# NGUYEN_LI.net
KiCad netlist of a schematic drawn in Altium Designer
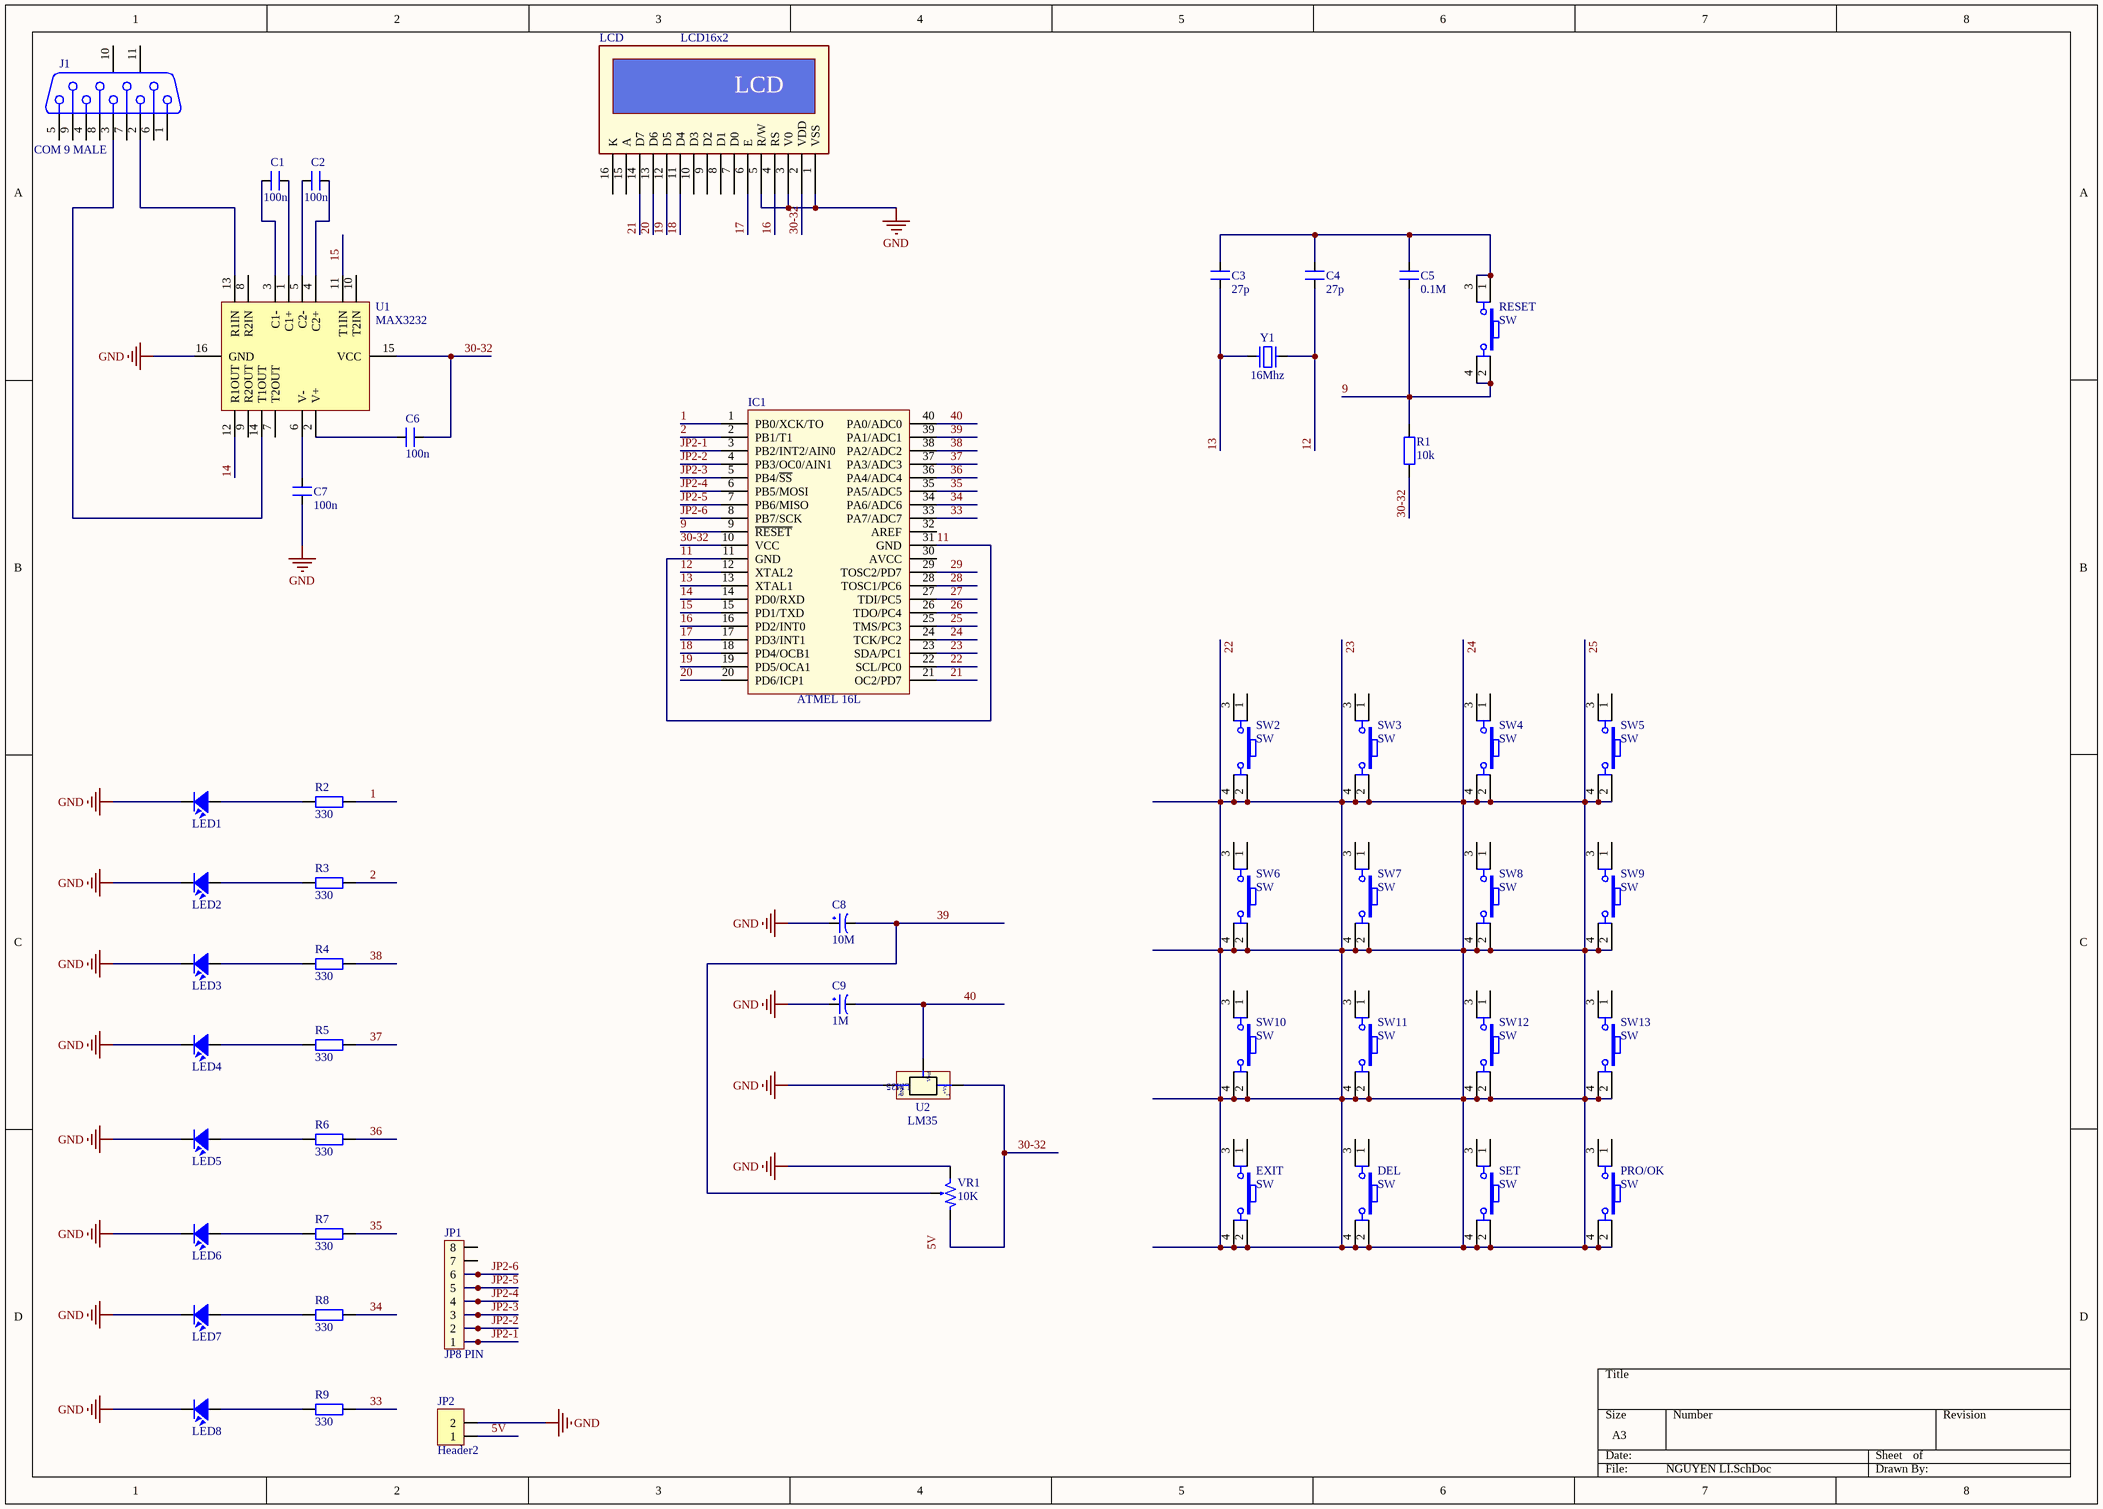
[diagram p0: NGUYEN LI.SchDoc]

(export (version "E")
  (design (tool "Eeschema 10.0.6"))
  (components
    (comp (ref "C1")
      (value "100n")
      (footprint "CN1")
      (description "Cap np  1pF - 472pF")
      (libsource (lib "Devzone_SCHLib") (part "CN1"))
    )
    (comp (ref "C2")
      (value "100n")
      (footprint "CN1")
      (description "Cap np  1pF - 472pF")
      (libsource (lib "Devzone_SCHLib") (part "CN1"))
    )
    (comp (ref "C3")
      (value "27p")
      (footprint "CN1")
      (description "Cap np  1pF - 472pF")
      (libsource (lib "syhaunguyen") (part "CN1"))
    )
    (comp (ref "C4")
      (value "27p")
      (footprint "CN1")
      (description "Cap np  1pF - 472pF")
      (libsource (lib "syhaunguyen") (part "CN1"))
    )
    (comp (ref "C5")
      (value "0.1M")
      (footprint "CN1")
      (description "Cap np  1pF - 472pF")
      (libsource (lib "syhaunguyen") (part "CN1"))
    )
    (comp (ref "C6")
      (value "100n")
      (footprint "CN1")
      (description "Cap np  1pF - 472pF")
      (libsource (lib "Devzone_SCHLib") (part "CN1"))
    )
    (comp (ref "C7")
      (value "100n")
      (footprint "CN1")
      (description "Cap np  1pF - 472pF")
      (libsource (lib "Devzone_SCHLib") (part "CN1"))
    )
    (comp (ref "C8")
      (value "10M")
      (footprint "CP1.5/3.4")
      (description "Cap 1000uF/16V - 220uF/50V")
      (libsource (lib "My Library (1)") (part "CP4"))
    )
    (comp (ref "C9")
      (value "1M")
      (footprint "CP1.5/3.4")
      (description "Cap 1000uF/16V - 220uF/50V")
      (libsource (lib "My Library (1)") (part "CP4"))
    )
    (comp (ref "DEL")
      (value "SW")
      (footprint "SW4B")
      (description "Switch button 4 pin")
      (libsource (lib "My Library (1)") (part "SW4"))
    )
    (comp (ref "EXIT")
      (value "SW")
      (footprint "SW4B")
      (description "Switch button 4 pin")
      (libsource (lib "My Library (1)") (part "SW4"))
    )
    (comp (ref "IC1")
      (value "ATMEL 16L")
      (footprint "DIP40/W0.6")
      (description "8-Bit AVR Microcontroller with 16K Bytes of In-System Programmable Flash Memory")
      (libsource (lib "Cty1") (part "Atmega16L"))
    )
    (comp (ref "J1")
      (value "COM 9 MALE")
      (footprint "DSB 9-M")
      (description "COM 9")
      (fields (field (name "PUBLISHER") "Altium Limited"))
      (libsource (lib "My Library (1)") (part "DSB9M"))
    )
    (comp (ref "JP1") (value "JP8 PIN") (footprint "JP8") (libsource (lib "My Library (1)") (part "JP8")))
    (comp (ref "JP2")
      (value "Header2")
      (footprint "Header2")
      (description "Header IDC, 2 x 1 Pin Vertical 2.54mm Pitch (Non-Boxed, Male)")
      (fields
        (field (name "MANUFACTURER") "Würth Elektronik eiSos GmbH")
        (field (name "PARTNO") "613002143121")
        (field (name "CREATED BY") "Karrer Zheng")
      )
      (libsource (lib "My Library (1)") (part "Header2"))
    )
    (comp (ref "LCD")
      (value "LCD16x2")
      (footprint "LCD16X2")
      (libsource (lib "Devzone_SCHLib") (part "LCD Text"))
    )
    (comp (ref "LED1")
      (value "LED")
      (footprint "LED-3")
      (description "LED Single colour Green and Red")
      (libsource (lib "syhaunguyen") (part "LED"))
    )
    (comp (ref "LED2")
      (value "LED")
      (footprint "LED-3")
      (description "LED Single colour Green and Red")
      (libsource (lib "syhaunguyen") (part "LED"))
    )
    (comp (ref "LED3")
      (value "LED")
      (footprint "LED-3")
      (description "LED Single colour Green and Red")
      (libsource (lib "syhaunguyen") (part "LED"))
    )
    (comp (ref "LED4")
      (value "LED")
      (footprint "LED-3")
      (description "LED Single colour Green and Red")
      (libsource (lib "syhaunguyen") (part "LED"))
    )
    (comp (ref "LED5")
      (value "LED")
      (footprint "LED-3")
      (description "LED Single colour Green and Red")
      (libsource (lib "syhaunguyen") (part "LED"))
    )
    (comp (ref "LED6")
      (value "LED")
      (footprint "LED-3")
      (description "LED Single colour Green and Red")
      (libsource (lib "syhaunguyen") (part "LED"))
    )
    (comp (ref "LED7")
      (value "LED")
      (footprint "LED-3")
      (description "LED Single colour Green and Red")
      (libsource (lib "syhaunguyen") (part "LED"))
    )
    (comp (ref "LED8")
      (value "LED")
      (footprint "LED-3")
      (description "LED Single colour Green and Red")
      (libsource (lib "syhaunguyen") (part "LED"))
    )
    (comp (ref "PRO/OK")
      (value "SW")
      (footprint "SW4B")
      (description "Switch button 4 pin")
      (libsource (lib "My Library (1)") (part "SW4"))
    )
    (comp (ref "R1")
      (value "10k")
      (footprint "R1/4W")
      (description "Resistor 1/4W")
      (libsource (lib "syhaunguyen") (part "R1/4W"))
    )
    (comp (ref "R2")
      (value "330")
      (footprint "R1/4W")
      (description "Resistor 1/4W")
      (libsource (lib "syhaunguyen") (part "R1/4W"))
    )
    (comp (ref "R3")
      (value "330")
      (footprint "R1/4W")
      (description "Resistor 1/4W")
      (libsource (lib "syhaunguyen") (part "R1/4W"))
    )
    (comp (ref "R4")
      (value "330")
      (footprint "R1/4W")
      (description "Resistor 1/4W")
      (libsource (lib "syhaunguyen") (part "R1/4W"))
    )
    (comp (ref "R5")
      (value "330")
      (footprint "R1/4W")
      (description "Resistor 1/4W")
      (libsource (lib "syhaunguyen") (part "R1/4W"))
    )
    (comp (ref "R6")
      (value "330")
      (footprint "R1/4W")
      (description "Resistor 1/4W")
      (libsource (lib "syhaunguyen") (part "R1/4W"))
    )
    (comp (ref "R7")
      (value "330")
      (footprint "R1/4W")
      (description "Resistor 1/4W")
      (libsource (lib "syhaunguyen") (part "R1/4W"))
    )
    (comp (ref "R8")
      (value "330")
      (footprint "R1/4W")
      (description "Resistor 1/4W")
      (libsource (lib "syhaunguyen") (part "R1/4W"))
    )
    (comp (ref "R9")
      (value "330")
      (footprint "R1/4W")
      (description "Resistor 1/4W")
      (libsource (lib "syhaunguyen") (part "R1/4W"))
    )
    (comp (ref "RESET")
      (value "SW")
      (footprint "SW4B")
      (description "Switch button 4 pin")
      (libsource (lib "My Library (1)") (part "SW4"))
    )
    (comp (ref "SET")
      (value "SW")
      (footprint "SW4B")
      (description "Switch button 4 pin")
      (libsource (lib "My Library (1)") (part "SW4"))
    )
    (comp (ref "SW2")
      (value "SW")
      (footprint "SW4B")
      (description "Switch button 4 pin")
      (libsource (lib "My Library (1)") (part "SW4"))
    )
    (comp (ref "SW3")
      (value "SW")
      (footprint "SW4B")
      (description "Switch button 4 pin")
      (libsource (lib "My Library (1)") (part "SW4"))
    )
    (comp (ref "SW4")
      (value "SW")
      (footprint "SW4B")
      (description "Switch button 4 pin")
      (libsource (lib "My Library (1)") (part "SW4"))
    )
    (comp (ref "SW5")
      (value "SW")
      (footprint "SW4B")
      (description "Switch button 4 pin")
      (libsource (lib "My Library (1)") (part "SW4"))
    )
    (comp (ref "SW6")
      (value "SW")
      (footprint "SW4B")
      (description "Switch button 4 pin")
      (libsource (lib "My Library (1)") (part "SW4"))
    )
    (comp (ref "SW7")
      (value "SW")
      (footprint "SW4B")
      (description "Switch button 4 pin")
      (libsource (lib "My Library (1)") (part "SW4"))
    )
    (comp (ref "SW8")
      (value "SW")
      (footprint "SW4B")
      (description "Switch button 4 pin")
      (libsource (lib "My Library (1)") (part "SW4"))
    )
    (comp (ref "SW9")
      (value "SW")
      (footprint "SW4B")
      (description "Switch button 4 pin")
      (libsource (lib "My Library (1)") (part "SW4"))
    )
    (comp (ref "SW10")
      (value "SW")
      (footprint "SW4B")
      (description "Switch button 4 pin")
      (libsource (lib "My Library (1)") (part "SW4"))
    )
    (comp (ref "SW11")
      (value "SW")
      (footprint "SW4B")
      (description "Switch button 4 pin")
      (libsource (lib "My Library (1)") (part "SW4"))
    )
    (comp (ref "SW12")
      (value "SW")
      (footprint "SW4B")
      (description "Switch button 4 pin")
      (libsource (lib "My Library (1)") (part "SW4"))
    )
    (comp (ref "SW13")
      (value "SW")
      (footprint "SW4B")
      (description "Switch button 4 pin")
      (libsource (lib "My Library (1)") (part "SW4"))
    )
    (comp (ref "U1")
      (value "MAX3232")
      (footprint "DIP16")
      (fields
        (field (name "MANUFACTURER PART NUMBER") "MAX232DR")
        (field (name "MANUFACTURER") "Texas Instruments")
      )
      (libsource (lib "TechMT.VN_Lib_Project v2") (part "MAX3232"))
    )
    (comp (ref "U2")
      (value "LM35")
      (footprint "QTO-92")
      (description "Teminal")
      (libsource (lib "My Library (1)") (part "LM35"))
    )
    (comp (ref "VR1")
      (value "10K")
      (footprint "VR1")
      (description "Var Resistor")
      (libsource (lib "My Library (1)") (part "VR1"))
    )
    (comp (ref "Y1")
      (value "16Mhz")
      (footprint "XT2")
      (description "Crystal For all Crystal 2pin.")
      (libsource (lib "syhaunguyen") (part "XT2"))
    )
  )
  (nets
    (net (code "1") (name "/1") (class "Default")
      (node (ref "IC1") (pin "1") (pinfunction "PB0/XCK/TO_1") (pintype "passive"))
      (node (ref "R2") (pin "2") (pinfunction "2_2") (pintype "passive"))
    )
    (net (code "2") (name "/2") (class "Default")
      (node (ref "IC1") (pin "2") (pinfunction "PB1/T1_2") (pintype "passive"))
      (node (ref "R3") (pin "2") (pinfunction "2_2") (pintype "passive"))
    )
    (net (code "3") (name "/5V") (class "Default")
      (node (ref "JP2") (pin "1") (pinfunction "1_1") (pintype "passive"))
    )
    (net (code "4") (name "/9") (class "Default")
      (node (ref "C5") (pin "2") (pinfunction "2_2") (pintype "passive"))
      (node (ref "IC1") (pin "9") (pinfunction "~{RESET}_9") (pintype "passive"))
      (node (ref "R1") (pin "1") (pinfunction "1_1") (pintype "passive"))
      (node (ref "RESET") (pin "2") (pintype "passive"))
      (node (ref "RESET") (pin "4") (pintype "passive"))
    )
    (net (code "5") (name "/11") (class "Default")
      (node (ref "IC1") (pin "11") (pinfunction "GND_11") (pintype "passive"))
      (node (ref "IC1") (pin "31") (pinfunction "GND_31") (pintype "passive"))
    )
    (net (code "6") (name "/12") (class "Default")
      (node (ref "C4") (pin "2") (pinfunction "2_2") (pintype "passive"))
      (node (ref "IC1") (pin "12") (pinfunction "XTAL2_12") (pintype "passive"))
      (node (ref "Y1") (pin "2") (pinfunction "2_2") (pintype "passive"))
    )
    (net (code "7") (name "/13") (class "Default")
      (node (ref "C3") (pin "2") (pinfunction "2_2") (pintype "passive"))
      (node (ref "IC1") (pin "13") (pinfunction "XTAL1_13") (pintype "passive"))
      (node (ref "Y1") (pin "1") (pinfunction "1_1") (pintype "passive"))
    )
    (net (code "8") (name "/14") (class "Default")
      (node (ref "IC1") (pin "14") (pinfunction "PD0/RXD_14") (pintype "passive"))
      (node (ref "U1") (pin "12") (pinfunction "R1OUT_12") (pintype "passive"))
    )
    (net (code "9") (name "/15") (class "Default")
      (node (ref "IC1") (pin "15") (pinfunction "PD1/TXD_15") (pintype "passive"))
      (node (ref "U1") (pin "11") (pinfunction "T1IN_11") (pintype "passive"))
    )
    (net (code "10") (name "/16") (class "Default")
      (node (ref "IC1") (pin "16") (pinfunction "PD2/INT0_16") (pintype "passive"))
      (node (ref "LCD") (pin "4") (pinfunction "RS_4") (pintype "passive"))
    )
    (net (code "11") (name "/17") (class "Default")
      (node (ref "IC1") (pin "17") (pinfunction "PD3/INT1_17") (pintype "passive"))
      (node (ref "LCD") (pin "6") (pinfunction "E_6") (pintype "passive"))
    )
    (net (code "12") (name "/18") (class "Default")
      (node (ref "IC1") (pin "18") (pinfunction "PD4/OCB1_18") (pintype "passive"))
      (node (ref "LCD") (pin "11") (pinfunction "D4_11") (pintype "passive"))
    )
    (net (code "13") (name "/19") (class "Default")
      (node (ref "IC1") (pin "19") (pinfunction "PD5/OCA1_19") (pintype "passive"))
      (node (ref "LCD") (pin "12") (pinfunction "D5_12") (pintype "passive"))
    )
    (net (code "14") (name "/20") (class "Default")
      (node (ref "IC1") (pin "20") (pinfunction "PD6/ICP1_20") (pintype "passive"))
      (node (ref "LCD") (pin "13") (pinfunction "D6_13") (pintype "passive"))
    )
    (net (code "15") (name "/21") (class "Default")
      (node (ref "IC1") (pin "21") (pinfunction "OC2/PD7_21") (pintype "passive"))
      (node (ref "LCD") (pin "14") (pinfunction "D7_14") (pintype "passive"))
    )
    (net (code "16") (name "/22") (class "Default")
      (node (ref "DEL") (pin "2") (pintype "passive"))
      (node (ref "DEL") (pin "4") (pintype "passive"))
      (node (ref "EXIT") (pin "2") (pintype "passive"))
      (node (ref "EXIT") (pin "4") (pintype "passive"))
      (node (ref "IC1") (pin "22") (pinfunction "SCL/PC0_22") (pintype "passive"))
      (node (ref "IC1") (pin "23") (pinfunction "SDA/PC1_23") (pintype "passive"))
      (node (ref "IC1") (pin "24") (pinfunction "TCK/PC2_24") (pintype "passive"))
      (node (ref "IC1") (pin "25") (pinfunction "TMS/PC3_25") (pintype "passive"))
      (node (ref "PRO/OK") (pin "2") (pintype "passive"))
      (node (ref "PRO/OK") (pin "4") (pintype "passive"))
      (node (ref "SET") (pin "2") (pintype "passive"))
      (node (ref "SET") (pin "4") (pintype "passive"))
      (node (ref "SW10") (pin "2") (pintype "passive"))
      (node (ref "SW10") (pin "4") (pintype "passive"))
      (node (ref "SW11") (pin "2") (pintype "passive"))
      (node (ref "SW11") (pin "4") (pintype "passive"))
      (node (ref "SW12") (pin "2") (pintype "passive"))
      (node (ref "SW12") (pin "4") (pintype "passive"))
      (node (ref "SW13") (pin "2") (pintype "passive"))
      (node (ref "SW13") (pin "4") (pintype "passive"))
      (node (ref "SW2") (pin "2") (pintype "passive"))
      (node (ref "SW2") (pin "4") (pintype "passive"))
      (node (ref "SW3") (pin "2") (pintype "passive"))
      (node (ref "SW3") (pin "4") (pintype "passive"))
      (node (ref "SW4") (pin "2") (pintype "passive"))
      (node (ref "SW4") (pin "4") (pintype "passive"))
      (node (ref "SW5") (pin "2") (pintype "passive"))
      (node (ref "SW5") (pin "4") (pintype "passive"))
      (node (ref "SW6") (pin "2") (pintype "passive"))
      (node (ref "SW6") (pin "4") (pintype "passive"))
      (node (ref "SW7") (pin "2") (pintype "passive"))
      (node (ref "SW7") (pin "4") (pintype "passive"))
      (node (ref "SW8") (pin "2") (pintype "passive"))
      (node (ref "SW8") (pin "4") (pintype "passive"))
      (node (ref "SW9") (pin "2") (pintype "passive"))
      (node (ref "SW9") (pin "4") (pintype "passive"))
    )
    (net (code "17") (name "/26") (class "Default")
      (node (ref "IC1") (pin "26") (pinfunction "TDO/PC4_26") (pintype "passive"))
    )
    (net (code "18") (name "/27") (class "Default")
      (node (ref "IC1") (pin "27") (pinfunction "TDI/PC5_27") (pintype "passive"))
    )
    (net (code "19") (name "/28") (class "Default")
      (node (ref "IC1") (pin "28") (pinfunction "TOSC1/PC6_28") (pintype "passive"))
    )
    (net (code "20") (name "/29") (class "Default")
      (node (ref "IC1") (pin "29") (pinfunction "TOSC2/PD7_29") (pintype "passive"))
    )
    (net (code "21") (name "/30-32") (class "Default")
      (node (ref "C6") (pin "2") (pinfunction "2_2") (pintype "passive"))
      (node (ref "IC1") (pin "10") (pinfunction "VCC_10") (pintype "passive"))
      (node (ref "LCD") (pin "2") (pinfunction "VDD_2") (pintype "passive"))
      (node (ref "R1") (pin "2") (pinfunction "2_2") (pintype "passive"))
      (node (ref "U1") (pin "15") (pinfunction "VCC_15") (pintype "power_in"))
      (node (ref "U2") (pin "1") (pinfunction "+Vs_1") (pintype "passive"))
      (node (ref "VR1") (pin "1") (pinfunction "1_1") (pintype "passive"))
    )
    (net (code "22") (name "/33") (class "Default")
      (node (ref "IC1") (pin "33") (pinfunction "PA7/ADC7_33") (pintype "passive"))
      (node (ref "R9") (pin "2") (pinfunction "2_2") (pintype "passive"))
    )
    (net (code "23") (name "/34") (class "Default")
      (node (ref "IC1") (pin "34") (pinfunction "PA6/ADC6_34") (pintype "passive"))
      (node (ref "R8") (pin "2") (pinfunction "2_2") (pintype "passive"))
    )
    (net (code "24") (name "/35") (class "Default")
      (node (ref "IC1") (pin "35") (pinfunction "PA5/ADC5_35") (pintype "passive"))
      (node (ref "R7") (pin "2") (pinfunction "2_2") (pintype "passive"))
    )
    (net (code "25") (name "/36") (class "Default")
      (node (ref "IC1") (pin "36") (pinfunction "PA4/ADC4_36") (pintype "passive"))
      (node (ref "R6") (pin "2") (pinfunction "2_2") (pintype "passive"))
    )
    (net (code "26") (name "/37") (class "Default")
      (node (ref "IC1") (pin "37") (pinfunction "PA3/ADC3_37") (pintype "passive"))
      (node (ref "R5") (pin "2") (pinfunction "2_2") (pintype "passive"))
    )
    (net (code "27") (name "/38") (class "Default")
      (node (ref "IC1") (pin "38") (pinfunction "PA2/ADC2_38") (pintype "passive"))
      (node (ref "R4") (pin "2") (pinfunction "2_2") (pintype "passive"))
    )
    (net (code "28") (name "/39") (class "Default")
      (node (ref "C8") (pin "2") (pinfunction "2_2") (pintype "passive"))
      (node (ref "IC1") (pin "39") (pinfunction "PA1/ADC1_39") (pintype "passive"))
      (node (ref "VR1") (pin "2") (pinfunction "2_2") (pintype "passive"))
    )
    (net (code "29") (name "/40") (class "Default")
      (node (ref "C9") (pin "2") (pinfunction "2_2") (pintype "passive"))
      (node (ref "IC1") (pin "40") (pinfunction "PA0/ADC0_40") (pintype "passive"))
      (node (ref "U2") (pin "2") (pinfunction "Vout_2") (pintype "passive"))
    )
    (net (code "30") (name "/JP2-1") (class "Default")
      (node (ref "IC1") (pin "3") (pinfunction "PB2/INT2/AIN0_3") (pintype "passive"))
      (node (ref "JP1") (pin "1") (pinfunction "1_1") (pintype "passive"))
    )
    (net (code "31") (name "/JP2-2") (class "Default")
      (node (ref "IC1") (pin "4") (pinfunction "PB3/OC0/AIN1_4") (pintype "passive"))
      (node (ref "JP1") (pin "2") (pinfunction "2_2") (pintype "passive"))
    )
    (net (code "32") (name "/JP2-3") (class "Default")
      (node (ref "IC1") (pin "5") (pinfunction "PB4/~{SS}_5") (pintype "passive"))
      (node (ref "JP1") (pin "3") (pinfunction "3_3") (pintype "passive"))
    )
    (net (code "33") (name "/JP2-4") (class "Default")
      (node (ref "IC1") (pin "6") (pinfunction "PB5/MOSI_6") (pintype "passive"))
      (node (ref "JP1") (pin "4") (pinfunction "4_4") (pintype "passive"))
    )
    (net (code "34") (name "/JP2-5") (class "Default")
      (node (ref "IC1") (pin "7") (pinfunction "PB6/MISO_7") (pintype "passive"))
      (node (ref "JP1") (pin "5") (pinfunction "5_5") (pintype "passive"))
    )
    (net (code "35") (name "/JP2-6") (class "Default")
      (node (ref "IC1") (pin "8") (pinfunction "PB7/SCK_8") (pintype "passive"))
      (node (ref "JP1") (pin "6") (pinfunction "6_6") (pintype "passive"))
    )
    (net (code "36") (name "GND") (class "Default")
      (node (ref "C7") (pin "1") (pinfunction "1_1") (pintype "passive"))
      (node (ref "C8") (pin "1") (pinfunction "1_1") (pintype "passive"))
      (node (ref "C9") (pin "1") (pinfunction "1_1") (pintype "passive"))
      (node (ref "JP2") (pin "2") (pinfunction "2_2") (pintype "passive"))
      (node (ref "LCD") (pin "1") (pinfunction "VSS_1") (pintype "passive"))
      (node (ref "LCD") (pin "3") (pinfunction "V0_3") (pintype "passive"))
      (node (ref "LCD") (pin "5") (pinfunction "R/W_5") (pintype "passive"))
      (node (ref "LED1") (pin "2") (pinfunction "2_2") (pintype "passive"))
      (node (ref "LED2") (pin "2") (pinfunction "2_2") (pintype "passive"))
      (node (ref "LED3") (pin "2") (pinfunction "2_2") (pintype "passive"))
      (node (ref "LED4") (pin "2") (pinfunction "2_2") (pintype "passive"))
      (node (ref "LED5") (pin "2") (pinfunction "2_2") (pintype "passive"))
      (node (ref "LED6") (pin "2") (pinfunction "2_2") (pintype "passive"))
      (node (ref "LED7") (pin "2") (pinfunction "2_2") (pintype "passive"))
      (node (ref "LED8") (pin "2") (pinfunction "2_2") (pintype "passive"))
      (node (ref "U1") (pin "16") (pinfunction "GND_16") (pintype "power_in"))
      (node (ref "U2") (pin "3") (pinfunction "-_3") (pintype "passive"))
      (node (ref "VR1") (pin "3") (pinfunction "3_3") (pintype "passive"))
    )
    (net (code "37") (name "Net-(C3-Pad1)") (class "Default")
      (node (ref "C3") (pin "1") (pinfunction "1_1") (pintype "passive"))
      (node (ref "C4") (pin "1") (pinfunction "1_1") (pintype "passive"))
      (node (ref "C5") (pin "1") (pinfunction "1_1") (pintype "passive"))
      (node (ref "RESET") (pin "1") (pintype "passive"))
      (node (ref "RESET") (pin "3") (pintype "passive"))
    )
    (net (code "38") (name "Net-(LED1-Pad1)") (class "Default")
      (node (ref "LED1") (pin "1") (pinfunction "1_1") (pintype "passive"))
      (node (ref "R2") (pin "1") (pinfunction "1_1") (pintype "passive"))
    )
    (net (code "39") (name "Net-(LED2-Pad1)") (class "Default")
      (node (ref "LED2") (pin "1") (pinfunction "1_1") (pintype "passive"))
      (node (ref "R3") (pin "1") (pinfunction "1_1") (pintype "passive"))
    )
    (net (code "40") (name "Net-(LED3-Pad1)") (class "Default")
      (node (ref "LED3") (pin "1") (pinfunction "1_1") (pintype "passive"))
      (node (ref "R4") (pin "1") (pinfunction "1_1") (pintype "passive"))
    )
    (net (code "41") (name "Net-(LED4-Pad1)") (class "Default")
      (node (ref "LED4") (pin "1") (pinfunction "1_1") (pintype "passive"))
      (node (ref "R5") (pin "1") (pinfunction "1_1") (pintype "passive"))
    )
    (net (code "42") (name "Net-(LED5-Pad1)") (class "Default")
      (node (ref "LED5") (pin "1") (pinfunction "1_1") (pintype "passive"))
      (node (ref "R6") (pin "1") (pinfunction "1_1") (pintype "passive"))
    )
    (net (code "43") (name "Net-(LED6-Pad1)") (class "Default")
      (node (ref "LED6") (pin "1") (pinfunction "1_1") (pintype "passive"))
      (node (ref "R7") (pin "1") (pinfunction "1_1") (pintype "passive"))
    )
    (net (code "44") (name "Net-(LED7-Pad1)") (class "Default")
      (node (ref "LED7") (pin "1") (pinfunction "1_1") (pintype "passive"))
      (node (ref "R8") (pin "1") (pinfunction "1_1") (pintype "passive"))
    )
    (net (code "45") (name "Net-(LED8-Pad1)") (class "Default")
      (node (ref "LED8") (pin "1") (pinfunction "1_1") (pintype "passive"))
      (node (ref "R9") (pin "1") (pinfunction "1_1") (pintype "passive"))
    )
    (net (code "46") (name "Net-(U1-C1+)") (class "Default")
      (node (ref "C1") (pin "2") (pinfunction "2_2") (pintype "passive"))
      (node (ref "U1") (pin "1") (pinfunction "C1+_1") (pintype "power_in"))
    )
    (net (code "47") (name "Net-(U1-C1-)") (class "Default")
      (node (ref "C1") (pin "1") (pinfunction "1_1") (pintype "passive"))
      (node (ref "U1") (pin "3") (pinfunction "C1-_3") (pintype "passive"))
    )
    (net (code "48") (name "Net-(U1-C2+)") (class "Default")
      (node (ref "C2") (pin "2") (pinfunction "2_2") (pintype "passive"))
      (node (ref "U1") (pin "4") (pinfunction "C2+_4") (pintype "passive"))
    )
    (net (code "49") (name "Net-(U1-C2-)") (class "Default")
      (node (ref "C2") (pin "1") (pinfunction "1_1") (pintype "passive"))
      (node (ref "U1") (pin "5") (pinfunction "C2-_5") (pintype "power_in"))
    )
    (net (code "50") (name "Net-(U1-R1IN)") (class "Default")
      (node (ref "J1") (pin "2") (pinfunction "2_2") (pintype "passive"))
      (node (ref "U1") (pin "13") (pinfunction "R1IN_13") (pintype "passive"))
    )
    (net (code "51") (name "Net-(U1-T1OUT)") (class "Default")
      (node (ref "J1") (pin "3") (pinfunction "3_3") (pintype "passive"))
      (node (ref "U1") (pin "14") (pinfunction "T1OUT_14") (pintype "power_in"))
    )
    (net (code "52") (name "Net-(U1-V+)") (class "Default")
      (node (ref "C6") (pin "1") (pinfunction "1_1") (pintype "passive"))
      (node (ref "U1") (pin "2") (pinfunction "V+_2") (pintype "passive"))
    )
    (net (code "53") (name "Net-(U1-V-)") (class "Default")
      (node (ref "C7") (pin "2") (pinfunction "2_2") (pintype "passive"))
      (node (ref "U1") (pin "6") (pinfunction "V-_6") (pintype "passive"))
    )
    (net (code "54") (name "unconnected-(DEL-Pad1)") (class "Default")
      (node (ref "DEL") (pin "1") (pintype "passive"))
    )
    (net (code "55") (name "unconnected-(DEL-Pad3)") (class "Default")
      (node (ref "DEL") (pin "3") (pintype "passive"))
    )
    (net (code "56") (name "unconnected-(EXIT-Pad1)") (class "Default")
      (node (ref "EXIT") (pin "1") (pintype "passive"))
    )
    (net (code "57") (name "unconnected-(EXIT-Pad3)") (class "Default")
      (node (ref "EXIT") (pin "3") (pintype "passive"))
    )
    (net (code "58") (name "unconnected-(IC1-AREF-Pad32)") (class "Default")
      (node (ref "IC1") (pin "32") (pinfunction "AREF_32") (pintype "passive"))
    )
    (net (code "59") (name "unconnected-(IC1-AVCC-Pad30)") (class "Default")
      (node (ref "IC1") (pin "30") (pinfunction "AVCC_30") (pintype "passive"))
    )
    (net (code "60") (name "unconnected-(J1-MH1-Pad10)") (class "Default")
      (node (ref "J1") (pin "10") (pinfunction "MH1_10") (pintype "passive"))
    )
    (net (code "61") (name "unconnected-(J1-MH2-Pad11)") (class "Default")
      (node (ref "J1") (pin "11") (pinfunction "MH2_11") (pintype "passive"))
    )
    (net (code "62") (name "unconnected-(J1-Pad1)") (class "Default")
      (node (ref "J1") (pin "1") (pinfunction "1_1") (pintype "passive"))
    )
    (net (code "63") (name "unconnected-(J1-Pad4)") (class "Default")
      (node (ref "J1") (pin "4") (pinfunction "4_4") (pintype "passive"))
    )
    (net (code "64") (name "unconnected-(J1-Pad5)") (class "Default")
      (node (ref "J1") (pin "5") (pinfunction "5_5") (pintype "passive"))
    )
    (net (code "65") (name "unconnected-(J1-Pad6)") (class "Default")
      (node (ref "J1") (pin "6") (pinfunction "6_6") (pintype "passive"))
    )
    (net (code "66") (name "unconnected-(J1-Pad7)") (class "Default")
      (node (ref "J1") (pin "7") (pinfunction "7_7") (pintype "passive"))
    )
    (net (code "67") (name "unconnected-(J1-Pad8)") (class "Default")
      (node (ref "J1") (pin "8") (pinfunction "8_8") (pintype "passive"))
    )
    (net (code "68") (name "unconnected-(J1-Pad9)") (class "Default")
      (node (ref "J1") (pin "9") (pinfunction "9_9") (pintype "passive"))
    )
    (net (code "69") (name "unconnected-(JP1-Pad7)") (class "Default")
      (node (ref "JP1") (pin "7") (pinfunction "7_7") (pintype "passive"))
    )
    (net (code "70") (name "unconnected-(JP1-Pad8)") (class "Default")
      (node (ref "JP1") (pin "8") (pinfunction "8_8") (pintype "passive"))
    )
    (net (code "71") (name "unconnected-(LCD-A-Pad15)") (class "Default")
      (node (ref "LCD") (pin "15") (pinfunction "A_15") (pintype "passive"))
    )
    (net (code "72") (name "unconnected-(LCD-D0-Pad7)") (class "Default")
      (node (ref "LCD") (pin "7") (pinfunction "D0_7") (pintype "passive"))
    )
    (net (code "73") (name "unconnected-(LCD-D1-Pad8)") (class "Default")
      (node (ref "LCD") (pin "8") (pinfunction "D1_8") (pintype "passive"))
    )
    (net (code "74") (name "unconnected-(LCD-D2-Pad9)") (class "Default")
      (node (ref "LCD") (pin "9") (pinfunction "D2_9") (pintype "passive"))
    )
    (net (code "75") (name "unconnected-(LCD-D3-Pad10)") (class "Default")
      (node (ref "LCD") (pin "10") (pinfunction "D3_10") (pintype "passive"))
    )
    (net (code "76") (name "unconnected-(LCD-K-Pad16)") (class "Default")
      (node (ref "LCD") (pin "16") (pinfunction "K_16") (pintype "passive"))
    )
    (net (code "77") (name "unconnected-(PRO/OK-Pad1)") (class "Default")
      (node (ref "PRO/OK") (pin "1") (pintype "passive"))
    )
    (net (code "78") (name "unconnected-(PRO/OK-Pad3)") (class "Default")
      (node (ref "PRO/OK") (pin "3") (pintype "passive"))
    )
    (net (code "79") (name "unconnected-(SET-Pad1)") (class "Default")
      (node (ref "SET") (pin "1") (pintype "passive"))
    )
    (net (code "80") (name "unconnected-(SET-Pad3)") (class "Default")
      (node (ref "SET") (pin "3") (pintype "passive"))
    )
    (net (code "81") (name "unconnected-(SW2-Pad1)") (class "Default")
      (node (ref "SW2") (pin "1") (pintype "passive"))
    )
    (net (code "82") (name "unconnected-(SW2-Pad3)") (class "Default")
      (node (ref "SW2") (pin "3") (pintype "passive"))
    )
    (net (code "83") (name "unconnected-(SW3-Pad1)") (class "Default")
      (node (ref "SW3") (pin "1") (pintype "passive"))
    )
    (net (code "84") (name "unconnected-(SW3-Pad3)") (class "Default")
      (node (ref "SW3") (pin "3") (pintype "passive"))
    )
    (net (code "85") (name "unconnected-(SW4-Pad1)") (class "Default")
      (node (ref "SW4") (pin "1") (pintype "passive"))
    )
    (net (code "86") (name "unconnected-(SW4-Pad3)") (class "Default")
      (node (ref "SW4") (pin "3") (pintype "passive"))
    )
    (net (code "87") (name "unconnected-(SW5-Pad1)") (class "Default")
      (node (ref "SW5") (pin "1") (pintype "passive"))
    )
    (net (code "88") (name "unconnected-(SW5-Pad3)") (class "Default")
      (node (ref "SW5") (pin "3") (pintype "passive"))
    )
    (net (code "89") (name "unconnected-(SW6-Pad1)") (class "Default")
      (node (ref "SW6") (pin "1") (pintype "passive"))
    )
    (net (code "90") (name "unconnected-(SW6-Pad3)") (class "Default")
      (node (ref "SW6") (pin "3") (pintype "passive"))
    )
    (net (code "91") (name "unconnected-(SW7-Pad1)") (class "Default")
      (node (ref "SW7") (pin "1") (pintype "passive"))
    )
    (net (code "92") (name "unconnected-(SW7-Pad3)") (class "Default")
      (node (ref "SW7") (pin "3") (pintype "passive"))
    )
    (net (code "93") (name "unconnected-(SW8-Pad1)") (class "Default")
      (node (ref "SW8") (pin "1") (pintype "passive"))
    )
    (net (code "94") (name "unconnected-(SW8-Pad3)") (class "Default")
      (node (ref "SW8") (pin "3") (pintype "passive"))
    )
    (net (code "95") (name "unconnected-(SW9-Pad1)") (class "Default")
      (node (ref "SW9") (pin "1") (pintype "passive"))
    )
    (net (code "96") (name "unconnected-(SW9-Pad3)") (class "Default")
      (node (ref "SW9") (pin "3") (pintype "passive"))
    )
    (net (code "97") (name "unconnected-(SW10-Pad1)") (class "Default")
      (node (ref "SW10") (pin "1") (pintype "passive"))
    )
    (net (code "98") (name "unconnected-(SW10-Pad3)") (class "Default")
      (node (ref "SW10") (pin "3") (pintype "passive"))
    )
    (net (code "99") (name "unconnected-(SW11-Pad1)") (class "Default")
      (node (ref "SW11") (pin "1") (pintype "passive"))
    )
    (net (code "100") (name "unconnected-(SW11-Pad3)") (class "Default")
      (node (ref "SW11") (pin "3") (pintype "passive"))
    )
    (net (code "101") (name "unconnected-(SW12-Pad1)") (class "Default")
      (node (ref "SW12") (pin "1") (pintype "passive"))
    )
    (net (code "102") (name "unconnected-(SW12-Pad3)") (class "Default")
      (node (ref "SW12") (pin "3") (pintype "passive"))
    )
    (net (code "103") (name "unconnected-(SW13-Pad1)") (class "Default")
      (node (ref "SW13") (pin "1") (pintype "passive"))
    )
    (net (code "104") (name "unconnected-(SW13-Pad3)") (class "Default")
      (node (ref "SW13") (pin "3") (pintype "passive"))
    )
    (net (code "105") (name "unconnected-(U1-R2IN-Pad8)") (class "Default")
      (node (ref "U1") (pin "8") (pinfunction "R2IN_8") (pintype "passive"))
    )
    (net (code "106") (name "unconnected-(U1-R2OUT-Pad9)") (class "Default")
      (node (ref "U1") (pin "9") (pinfunction "R2OUT_9") (pintype "passive"))
    )
    (net (code "107") (name "unconnected-(U1-T2IN-Pad10)") (class "Default")
      (node (ref "U1") (pin "10") (pinfunction "T2IN_10") (pintype "passive"))
    )
    (net (code "108") (name "unconnected-(U1-T2OUT-Pad7)") (class "Default")
      (node (ref "U1") (pin "7") (pinfunction "T2OUT_7") (pintype "passive"))
    )
  )
)
